# iNodeSocket-v0_1.net
KiCad netlist of a schematic drawn in EAGLE
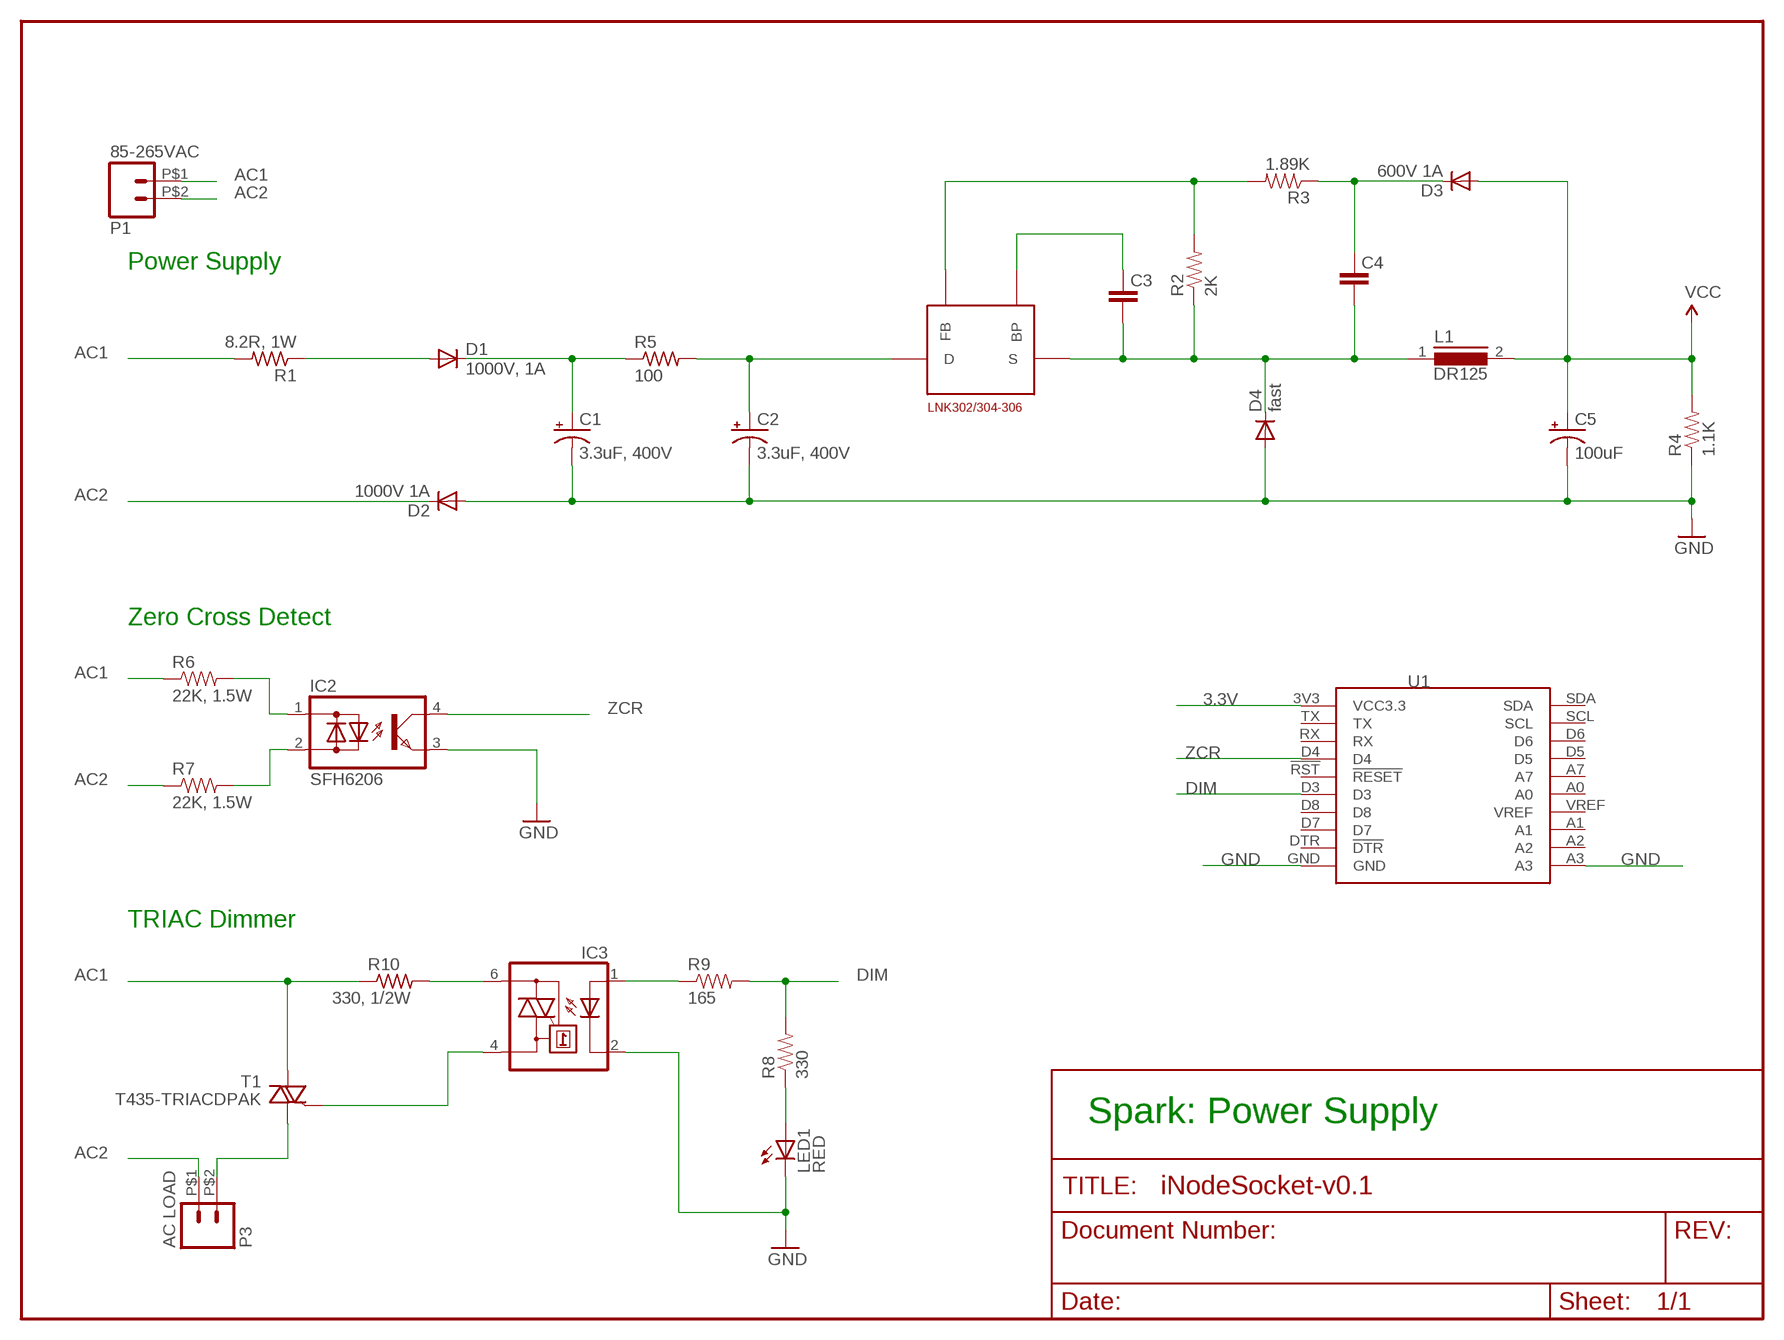
[diagram p0: schematic, sheet 1]

(export (version "E")
  (design (tool "Eeschema 10.0.6"))
  (components
    (comp (ref "C1")
      (value "3.3uF, 400V")
      (footprint "eagle-import:E3,5-8")
      (libsource (lib "eagle-import") (part "CPOL-USE3.5-8"))
    )
    (comp (ref "C2")
      (value "3.3uF, 400V")
      (footprint "eagle-import:E3,5-8")
      (libsource (lib "eagle-import") (part "CPOL-USE3.5-8"))
    )
    (comp (ref "C3")
      (value "0.1uF")
      (footprint "eagle-import:0603-CAP")
      (libsource (lib "eagle-import") (part "CAP0603-CAP"))
    )
    (comp (ref "C4")
      (value "10uF, 50V")
      (footprint "eagle-import:0805")
      (libsource (lib "eagle-import") (part "CAP0805"))
    )
    (comp (ref "C5")
      (value "100uF")
      (footprint "eagle-import:EIA3528")
      (libsource (lib "eagle-import") (part "CAP_POL3528"))
    )
    (comp (ref "D1")
      (value "1000V, 1A")
      (footprint "eagle-import:SMA-DIODE")
      (libsource (lib "eagle-import") (part "DIODESMA"))
    )
    (comp (ref "D2")
      (value "1000V 1A")
      (footprint "eagle-import:SMA-DIODE")
      (libsource (lib "eagle-import") (part "DIODESMA"))
    )
    (comp (ref "D3")
      (value "600V 1A")
      (footprint "eagle-import:SMA-DIODE")
      (libsource (lib "eagle-import") (part "DIODESMA"))
    )
    (comp (ref "D4")
      (value "fast")
      (footprint "eagle-import:SMA-DIODE")
      (libsource (lib "eagle-import") (part "DIODESMA"))
    )
    (comp (ref "IC1")
      (value "LNK302/304-306")
      (footprint "eagle-import:SMD-8B")
      (libsource (lib "eagle-import") (part "LNK302/304-306"))
    )
    (comp (ref "IC2")
      (value "SFH6206")
      (footprint "eagle-import:DIL4-SMD")
      (fields (field (name "MF") "VISHAY/TELEFUNKEN") (field (name "MPN") "SFH6206-3"))
      (libsource (lib "eagle-import") (part "SFH6206"))
    )
    (comp (ref "IC3")
      (value "MOC3031S")
      (footprint "eagle-import:DIL6-SMD")
      (fields
        (field (name "MF") "FAIRCHILD SEMICONDUCTOR")
        (field (name "MPN") "MOC3031SM")
        (field (name "MPN_1") "MOC3031SM")
        (field (name "OC_FARNELL") "unknown")
        (field (name "OC_NEWARK") "34C1335")
      )
      (libsource (lib "eagle-import") (part "MOC30S31"))
    )
    (comp (ref "L1")
      (value "DR125")
      (footprint "eagle-import:DR125")
      (libsource (lib "eagle-import") (part "DR125"))
    )
    (comp (ref "LED1")
      (value "RED")
      (footprint "eagle-import:LED-0603")
      (libsource (lib "eagle-import") (part "LED0603"))
    )
    (comp (ref "P1")
      (value "85-265VAC")
      (footprint "eagle-import:1X02_BIG")
      (libsource (lib "eagle-import") (part "M02PTH2"))
    )
    (comp (ref "P3")
      (value "AC LOAD")
      (footprint "eagle-import:1X02_BIG")
      (libsource (lib "eagle-import") (part "M02PTH2"))
    )
    (comp (ref "R1")
      (value "8.2R, 1W")
      (footprint "eagle-import:0207_10")
      (libsource (lib "eagle-import") (part "R-US_0207/10"))
    )
    (comp (ref "R2")
      (value "2K")
      (footprint "eagle-import:0805")
      (libsource (lib "eagle-import") (part "RESISTOR0805-RES"))
    )
    (comp (ref "R3")
      (value "1.89K")
      (footprint "eagle-import:0805")
      (libsource (lib "eagle-import") (part "RESISTOR0805-RES"))
    )
    (comp (ref "R4")
      (value "1.1K")
      (footprint "eagle-import:0603-RES")
      (libsource (lib "eagle-import") (part "RESISTOR0603-RES"))
    )
    (comp (ref "R5")
      (value "100")
      (footprint "eagle-import:0204_7")
      (libsource (lib "eagle-import") (part "R-US_0204/7"))
    )
    (comp (ref "R6")
      (value "22K, 1.5W")
      (footprint "eagle-import:R2512")
      (libsource (lib "eagle-import") (part "RESISTOR2512"))
    )
    (comp (ref "R7")
      (value "22K, 1.5W")
      (footprint "eagle-import:R2512")
      (libsource (lib "eagle-import") (part "RESISTOR2512"))
    )
    (comp (ref "R8")
      (value "330")
      (footprint "eagle-import:0805")
      (libsource (lib "eagle-import") (part "RESISTOR0805-RES"))
    )
    (comp (ref "R9")
      (value "165")
      (footprint "eagle-import:0805")
      (libsource (lib "eagle-import") (part "RESISTOR0805-RES"))
    )
    (comp (ref "R10")
      (value "330, 1/2W")
      (footprint "eagle-import:R1210")
      (libsource (lib "eagle-import") (part "R-US_R1210"))
    )
    (comp (ref "T1")
      (value "T435-TRIACDPAK")
      (footprint "eagle-import:TO252")
      (libsource (lib "eagle-import") (part "T435-TRIACDPAK"))
    )
    (comp (ref "U1")
      (value "BEE-IOTBEE-IOTBEE-SOCKET")
      (footprint "eagle-import:IOT_BEE_SMD")
      (libsource (lib "eagle-import") (part "BEE-IOTBEE-IOTBEE-SOCKET"))
    )
  )
  (nets
    (net (code "1") (name "/AC1") (class "Default")
      (node (ref "P1") (pin "P$1") (pinfunction "1_P$1") (pintype "passive"))
      (node (ref "R1") (pin "2") (pinfunction "2_2") (pintype "passive"))
      (node (ref "R10") (pin "1") (pinfunction "1_1") (pintype "passive"))
      (node (ref "R6") (pin "1") (pinfunction "1_1") (pintype "passive"))
      (node (ref "T1") (pin "2") (pinfunction "A2_2") (pintype "passive"))
    )
    (net (code "2") (name "/AC2") (class "Default")
      (node (ref "D2") (pin "C") (pinfunction "C_C") (pintype "passive"))
      (node (ref "P1") (pin "P$2") (pinfunction "2_P$2") (pintype "passive"))
      (node (ref "P3") (pin "P$1") (pinfunction "1_P$1") (pintype "passive"))
      (node (ref "R7") (pin "1") (pinfunction "1_1") (pintype "passive"))
    )
    (net (code "3") (name "/DIM") (class "Default")
      (node (ref "R8") (pin "2") (pinfunction "2_2") (pintype "passive"))
      (node (ref "R9") (pin "2") (pinfunction "2_2") (pintype "passive"))
      (node (ref "U1") (pin "D3") (pinfunction "D3_D3") (pintype "bidirectional"))
    )
    (net (code "4") (name "/ZCR") (class "Default")
      (node (ref "IC2") (pin "4") (pinfunction "C_4") (pintype "passive"))
      (node (ref "U1") (pin "D4") (pinfunction "D4_D4") (pintype "bidirectional"))
    )
    (net (code "5") (name "GND") (class "Default")
      (node (ref "C1") (pin "-") (pinfunction "-_-") (pintype "passive"))
      (node (ref "C2") (pin "-") (pinfunction "-_-") (pintype "passive"))
      (node (ref "C5") (pin "C") (pinfunction "-_C") (pintype "passive"))
      (node (ref "D2") (pin "A") (pinfunction "A_A") (pintype "passive"))
      (node (ref "D4") (pin "A") (pinfunction "A_A") (pintype "passive"))
      (node (ref "IC2") (pin "3") (pinfunction "E_3") (pintype "passive"))
      (node (ref "IC3") (pin "2") (pinfunction "C_2") (pintype "passive"))
      (node (ref "LED1") (pin "C") (pinfunction "C_C") (pintype "passive"))
      (node (ref "R4") (pin "1") (pinfunction "1_1") (pintype "passive"))
      (node (ref "U1") (pin "A3") (pinfunction "A3_A3") (pintype "bidirectional"))
      (node (ref "U1") (pin "GND") (pinfunction "GND_GND") (pintype "bidirectional"))
    )
    (net (code "6") (name "Net-(C1-Pad+)") (class "Default")
      (node (ref "C1") (pin "+") (pinfunction "+_+") (pintype "passive"))
      (node (ref "D1") (pin "C") (pinfunction "C_C") (pintype "passive"))
      (node (ref "R5") (pin "1") (pinfunction "1_1") (pintype "passive"))
    )
    (net (code "7") (name "Net-(C2-Pad+)") (class "Default")
      (node (ref "C2") (pin "+") (pinfunction "+_+") (pintype "passive"))
      (node (ref "IC1") (pin "D") (pinfunction "D_D") (pintype "bidirectional"))
      (node (ref "R5") (pin "2") (pinfunction "2_2") (pintype "passive"))
    )
    (net (code "8") (name "Net-(C3-Pad2)") (class "Default")
      (node (ref "C3") (pin "2") (pinfunction "2_2") (pintype "passive"))
      (node (ref "IC1") (pin "BP") (pinfunction "BP_BP") (pintype "bidirectional"))
    )
    (net (code "9") (name "Net-(C4-Pad2)") (class "Default")
      (node (ref "C4") (pin "2") (pinfunction "2_2") (pintype "passive"))
      (node (ref "D3") (pin "C") (pinfunction "C_C") (pintype "passive"))
      (node (ref "R3") (pin "1") (pinfunction "1_1") (pintype "passive"))
    )
    (net (code "10") (name "Net-(D1-PadA)") (class "Default")
      (node (ref "D1") (pin "A") (pinfunction "A_A") (pintype "passive"))
      (node (ref "R1") (pin "1") (pinfunction "1_1") (pintype "passive"))
    )
    (net (code "11") (name "Net-(IC1-PadFB)") (class "Default")
      (node (ref "IC1") (pin "FB") (pinfunction "FB_FB") (pintype "bidirectional"))
      (node (ref "R2") (pin "2") (pinfunction "2_2") (pintype "passive"))
      (node (ref "R3") (pin "2") (pinfunction "2_2") (pintype "passive"))
    )
    (net (code "12") (name "Net-(IC1-S)") (class "Default")
      (node (ref "C3") (pin "1") (pinfunction "1_1") (pintype "passive"))
      (node (ref "C4") (pin "1") (pinfunction "1_1") (pintype "passive"))
      (node (ref "D4") (pin "C") (pinfunction "C_C") (pintype "passive"))
      (node (ref "IC1") (pin "S1") (pinfunction "S_S1") (pintype "bidirectional"))
      (node (ref "L1") (pin "1") (pinfunction "1_1") (pintype "passive"))
      (node (ref "R2") (pin "1") (pinfunction "1_1") (pintype "passive"))
    )
    (net (code "13") (name "Net-(IC2-AC1)") (class "Default")
      (node (ref "IC2") (pin "1") (pinfunction "AC1_1") (pintype "passive"))
      (node (ref "R6") (pin "2") (pinfunction "2_2") (pintype "passive"))
    )
    (net (code "14") (name "Net-(IC2-AC2)") (class "Default")
      (node (ref "IC2") (pin "2") (pinfunction "AC2_2") (pintype "passive"))
      (node (ref "R7") (pin "2") (pinfunction "2_2") (pintype "passive"))
    )
    (net (code "15") (name "Net-(IC3-A)") (class "Default")
      (node (ref "IC3") (pin "1") (pinfunction "A_1") (pintype "passive"))
      (node (ref "R9") (pin "1") (pinfunction "1_1") (pintype "passive"))
    )
    (net (code "16") (name "Net-(IC3-A1)") (class "Default")
      (node (ref "IC3") (pin "4") (pinfunction "A1_4") (pintype "passive"))
      (node (ref "T1") (pin "3") (pinfunction "G_3") (pintype "passive"))
    )
    (net (code "17") (name "Net-(IC3-A2)") (class "Default")
      (node (ref "IC3") (pin "6") (pinfunction "A2_6") (pintype "passive"))
      (node (ref "R10") (pin "2") (pinfunction "2_2") (pintype "passive"))
    )
    (net (code "18") (name "Net-(LED1-PadA)") (class "Default")
      (node (ref "LED1") (pin "A") (pinfunction "A_A") (pintype "passive"))
      (node (ref "R8") (pin "1") (pinfunction "1_1") (pintype "passive"))
    )
    (net (code "19") (name "Net-(P3-2)") (class "Default")
      (node (ref "P3") (pin "P$2") (pinfunction "2_P$2") (pintype "passive"))
      (node (ref "T1") (pin "1") (pinfunction "A1_1") (pintype "passive"))
    )
    (net (code "20") (name "VCC") (class "Default")
      (node (ref "C5") (pin "A") (pinfunction "+_A") (pintype "passive"))
      (node (ref "D3") (pin "A") (pinfunction "A_A") (pintype "passive"))
      (node (ref "L1") (pin "2") (pinfunction "2_2") (pintype "passive"))
      (node (ref "R4") (pin "2") (pinfunction "2_2") (pintype "passive"))
      (node (ref "U1") (pin "3V3") (pinfunction "VCC3.3_3V3") (pintype "bidirectional"))
    )
    (net (code "21") (name "unconnected-(U1-PadA0)") (class "Default")
      (node (ref "U1") (pin "A0") (pinfunction "A0_A0") (pintype "bidirectional"))
    )
    (net (code "22") (name "unconnected-(U1-PadA1)") (class "Default")
      (node (ref "U1") (pin "A1") (pinfunction "A1_A1") (pintype "bidirectional"))
    )
    (net (code "23") (name "unconnected-(U1-PadA2)") (class "Default")
      (node (ref "U1") (pin "A2") (pinfunction "A2_A2") (pintype "bidirectional"))
    )
    (net (code "24") (name "unconnected-(U1-PadA7)") (class "Default")
      (node (ref "U1") (pin "A7") (pinfunction "A7_A7") (pintype "bidirectional"))
    )
    (net (code "25") (name "unconnected-(U1-PadD5)") (class "Default")
      (node (ref "U1") (pin "D5") (pinfunction "D5_D5") (pintype "bidirectional"))
    )
    (net (code "26") (name "unconnected-(U1-PadD6)") (class "Default")
      (node (ref "U1") (pin "D6") (pinfunction "D6_D6") (pintype "bidirectional"))
    )
    (net (code "27") (name "unconnected-(U1-PadD7)") (class "Default")
      (node (ref "U1") (pin "D7") (pinfunction "D7_D7") (pintype "bidirectional"))
    )
    (net (code "28") (name "unconnected-(U1-PadD8)") (class "Default")
      (node (ref "U1") (pin "D8") (pinfunction "D8_D8") (pintype "bidirectional"))
    )
    (net (code "29") (name "unconnected-(U1-PadRX)") (class "Default")
      (node (ref "U1") (pin "RX") (pinfunction "RX_RX") (pintype "bidirectional"))
    )
    (net (code "30") (name "unconnected-(U1-PadSCL)") (class "Default")
      (node (ref "U1") (pin "SCL") (pinfunction "SCL_SCL") (pintype "bidirectional"))
    )
    (net (code "31") (name "unconnected-(U1-PadSDA)") (class "Default")
      (node (ref "U1") (pin "SDA") (pinfunction "SDA_SDA") (pintype "bidirectional"))
    )
    (net (code "32") (name "unconnected-(U1-PadTX)") (class "Default")
      (node (ref "U1") (pin "TX") (pinfunction "TX_TX") (pintype "bidirectional"))
    )
    (net (code "33") (name "unconnected-(U1-PadVREF)") (class "Default")
      (node (ref "U1") (pin "VREF") (pinfunction "VREF_VREF") (pintype "bidirectional"))
    )
    (net (code "34") (name "unconnected-(U1-~{DTR}-PadDTR)") (class "Default")
      (node (ref "U1") (pin "DTR") (pinfunction "~{DTR}_DTR") (pintype "bidirectional"))
    )
    (net (code "35") (name "unconnected-(U1-~{RESET}-Pad!RST)") (class "Default")
      (node (ref "U1") (pin "!RST") (pinfunction "~{RESET}_!RST") (pintype "bidirectional"))
    )
  )
)
